# Module_main.net
KiCad netlist of a schematic drawn in Altium Designer
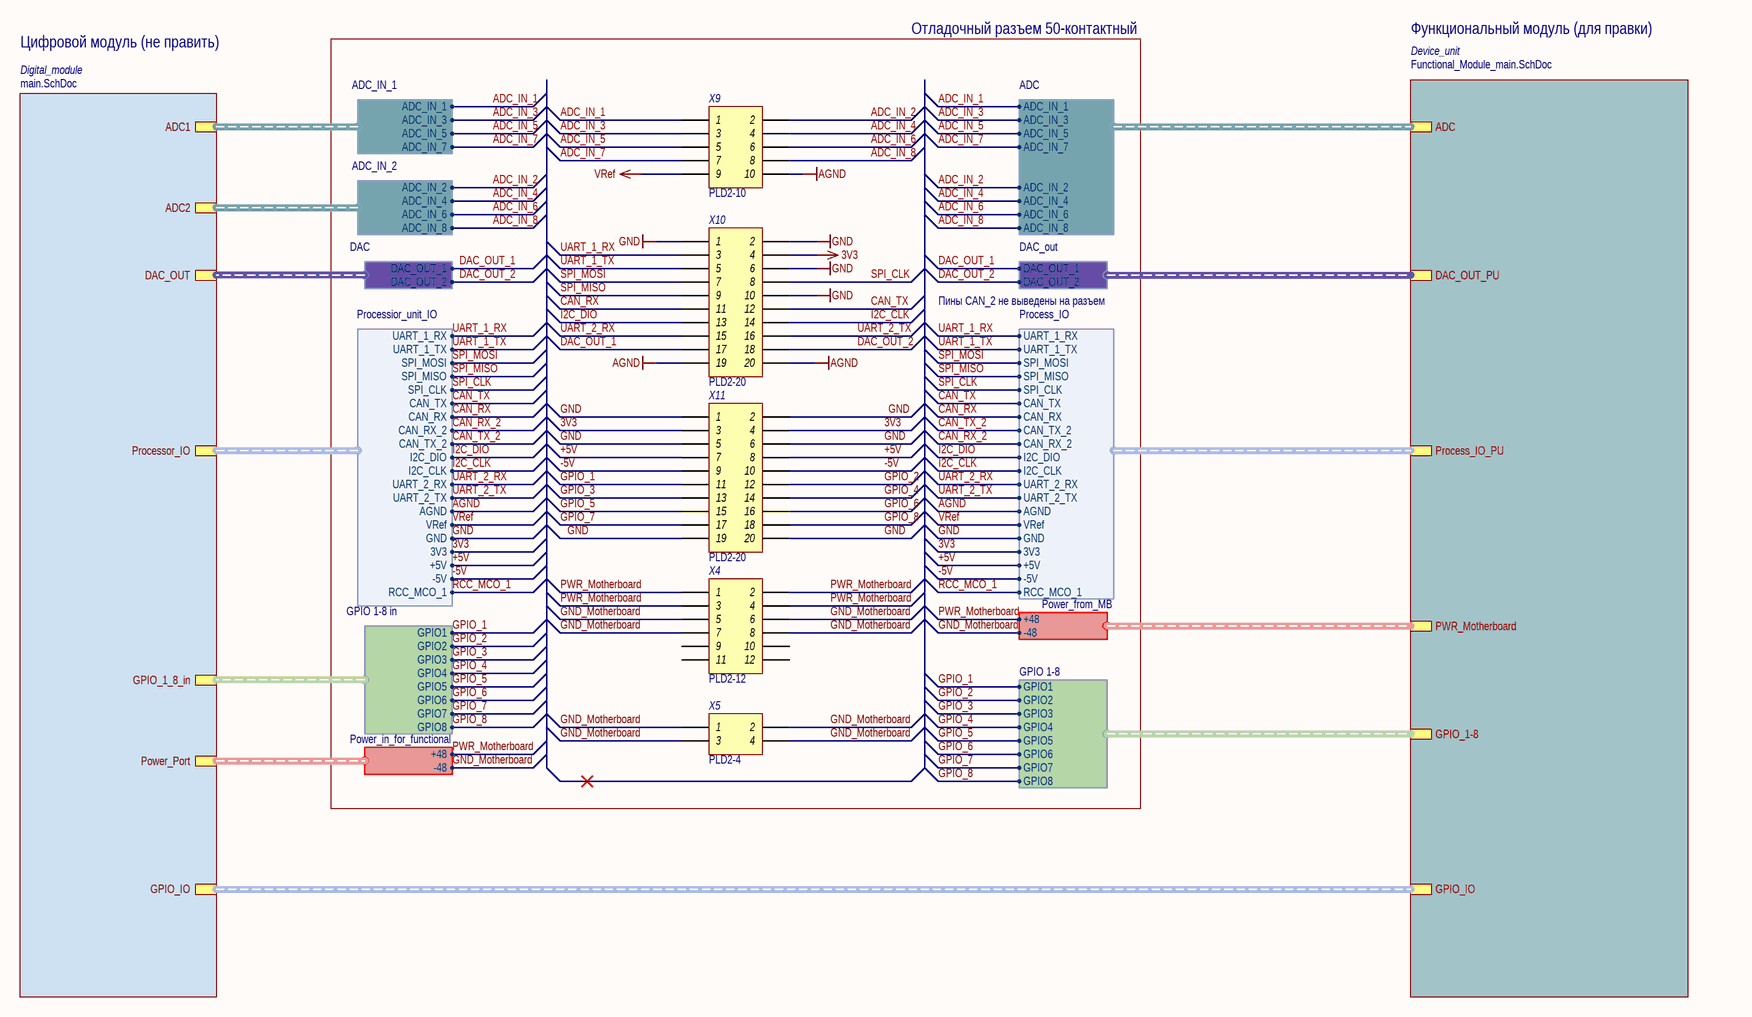
[diagram p0: Module_main.SchDoc]

(export (version "E")
  (design (tool "Eeschema 10.0.6"))
  (components
    (comp (ref "X4")
      (value "Header 2X6")
      (footprint "PLD2-12R 2.54")
      (description "Header, 12-Pin, Dual row")
      (fields (field (name "НАИМЕНОВАНИЕ") "PLD2-12"))
      (libsource (lib "Connector") (part "PLD2-12"))
    )
    (comp (ref "X5")
      (value "Header 2X4")
      (footprint "PLD2-4 R 2.54")
      (description "Header, 4-Pin, Dual row")
      (fields (field (name "НАИМЕНОВАНИЕ") "PLD2-4"))
      (libsource (lib "Connector") (part "PLD2-4"))
    )
    (comp (ref "X9")
      (value "Header 2X10")
      (footprint "PBD2-10s")
      (description "Header, 10-Pin, Dual row")
      (fields (field (name "НАИМЕНОВАНИЕ") "PLD2-10"))
      (libsource (lib "Connector") (part "PLD2-10"))
    )
    (comp (ref "X10")
      (value "Header 2X10")
      (footprint "PBD2-20s")
      (description "Header, 12-Pin, Dual row")
      (fields (field (name "НАИМЕНОВАНИЕ") "PLD2-20"))
      (libsource (lib "Connector") (part "PLD2-20"))
    )
    (comp (ref "X11")
      (value "Header 2X10")
      (footprint "PBD2-20s")
      (description "Header, 12-Pin, Dual row")
      (fields (field (name "НАИМЕНОВАНИЕ") "PLD2-20"))
      (libsource (lib "Connector") (part "PLD2-20"))
    )
  )
  (nets
    (net (code "11") (name "/+5V") (class "Default")
      (node (ref "X11") (pin "7") (pinfunction "7_7") (pintype "passive"))
      (node (ref "X11") (pin "8") (pinfunction "8_8") (pintype "passive"))
    )
    (net (code "12") (name "/-5V") (class "Default")
      (node (ref "X11") (pin "10") (pinfunction "10_10") (pintype "passive"))
      (node (ref "X11") (pin "9") (pinfunction "9_9") (pintype "passive"))
    )
    (net (code "13") (name "/ADC_IN_1") (class "Default")
      (node (ref "X9") (pin "1") (pinfunction "1_1") (pintype "passive"))
    )
    (net (code "14") (name "/ADC_IN_2") (class "Default")
      (node (ref "X9") (pin "2") (pinfunction "2_2") (pintype "passive"))
    )
    (net (code "15") (name "/ADC_IN_3") (class "Default")
      (node (ref "X9") (pin "3") (pinfunction "3_3") (pintype "passive"))
    )
    (net (code "16") (name "/ADC_IN_4") (class "Default")
      (node (ref "X9") (pin "4") (pinfunction "4_4") (pintype "passive"))
    )
    (net (code "17") (name "/ADC_IN_5") (class "Default")
      (node (ref "X9") (pin "5") (pinfunction "5_5") (pintype "passive"))
    )
    (net (code "18") (name "/ADC_IN_6") (class "Default")
      (node (ref "X9") (pin "6") (pinfunction "6_6") (pintype "passive"))
    )
    (net (code "19") (name "/ADC_IN_7") (class "Default")
      (node (ref "X9") (pin "7") (pinfunction "7_7") (pintype "passive"))
    )
    (net (code "20") (name "/ADC_IN_8") (class "Default")
      (node (ref "X9") (pin "8") (pinfunction "8_8") (pintype "passive"))
    )
    (net (code "21") (name "/CAN_RX") (class "Default")
      (node (ref "X10") (pin "11") (pinfunction "11_11") (pintype "passive"))
    )
    (net (code "23") (name "/CAN_TX") (class "Default")
      (node (ref "X10") (pin "12") (pinfunction "12_12") (pintype "passive"))
    )
    (net (code "25") (name "/DAC_OUT_1") (class "Default")
      (node (ref "X10") (pin "17") (pinfunction "17_17") (pintype "passive"))
    )
    (net (code "26") (name "/DAC_OUT_2") (class "Default")
      (node (ref "X10") (pin "18") (pinfunction "18_18") (pintype "passive"))
    )
    (net (code "27") (name "/GND_Motherboard") (class "Default")
      (node (ref "X4") (pin "5") (pinfunction "5_5") (pintype "passive"))
      (node (ref "X4") (pin "6") (pinfunction "6_6") (pintype "passive"))
      (node (ref "X4") (pin "7") (pinfunction "7_7") (pintype "passive"))
      (node (ref "X4") (pin "8") (pinfunction "8_8") (pintype "passive"))
      (node (ref "X5") (pin "1") (pinfunction "1_1") (pintype "passive"))
      (node (ref "X5") (pin "2") (pinfunction "2_2") (pintype "passive"))
      (node (ref "X5") (pin "3") (pinfunction "3_3") (pintype "passive"))
      (node (ref "X5") (pin "4") (pinfunction "4_4") (pintype "passive"))
    )
    (net (code "28") (name "/GPIO_1") (class "Default")
      (node (ref "X11") (pin "11") (pinfunction "11_11") (pintype "passive"))
    )
    (net (code "29") (name "/GPIO_2") (class "Default")
      (node (ref "X11") (pin "12") (pinfunction "12_12") (pintype "passive"))
    )
    (net (code "30") (name "/GPIO_3") (class "Default")
      (node (ref "X11") (pin "13") (pinfunction "13_13") (pintype "passive"))
    )
    (net (code "31") (name "/GPIO_4") (class "Default")
      (node (ref "X11") (pin "14") (pinfunction "14_14") (pintype "passive"))
    )
    (net (code "32") (name "/GPIO_5") (class "Default")
      (node (ref "X11") (pin "15") (pinfunction "15_15") (pintype "passive"))
    )
    (net (code "33") (name "/GPIO_6") (class "Default")
      (node (ref "X11") (pin "16") (pinfunction "16_16") (pintype "passive"))
    )
    (net (code "34") (name "/GPIO_7") (class "Default")
      (node (ref "X11") (pin "17") (pinfunction "17_17") (pintype "passive"))
    )
    (net (code "35") (name "/GPIO_8") (class "Default")
      (node (ref "X11") (pin "18") (pinfunction "18_18") (pintype "passive"))
    )
    (net (code "37") (name "/I2C_CLK") (class "Default")
      (node (ref "X10") (pin "14") (pinfunction "14_14") (pintype "passive"))
    )
    (net (code "38") (name "/I2C_DIO") (class "Default")
      (node (ref "X10") (pin "13") (pinfunction "13_13") (pintype "passive"))
    )
    (net (code "39") (name "/PWR_Motherboard") (class "Default")
      (node (ref "X4") (pin "1") (pinfunction "1_1") (pintype "passive"))
      (node (ref "X4") (pin "2") (pinfunction "2_2") (pintype "passive"))
      (node (ref "X4") (pin "3") (pinfunction "3_3") (pintype "passive"))
      (node (ref "X4") (pin "4") (pinfunction "4_4") (pintype "passive"))
    )
    (net (code "41") (name "/SPI_CLK") (class "Default")
      (node (ref "X10") (pin "8") (pinfunction "8_8") (pintype "passive"))
    )
    (net (code "42") (name "/SPI_MISO") (class "Default")
      (node (ref "X10") (pin "9") (pinfunction "9_9") (pintype "passive"))
    )
    (net (code "43") (name "/SPI_MOSI") (class "Default")
      (node (ref "X10") (pin "7") (pinfunction "7_7") (pintype "passive"))
    )
    (net (code "44") (name "/UART_1_RX") (class "Default")
      (node (ref "X10") (pin "3") (pinfunction "3_3") (pintype "passive"))
    )
    (net (code "45") (name "/UART_1_TX") (class "Default")
      (node (ref "X10") (pin "5") (pinfunction "5_5") (pintype "passive"))
    )
    (net (code "46") (name "/UART_2_RX") (class "Default")
      (node (ref "X10") (pin "15") (pinfunction "15_15") (pintype "passive"))
    )
    (net (code "47") (name "/UART_2_TX") (class "Default")
      (node (ref "X10") (pin "16") (pinfunction "16_16") (pintype "passive"))
    )
    (net (code "59") (name "3V3") (class "Default")
      (node (ref "X10") (pin "4") (pinfunction "4_4") (pintype "passive"))
      (node (ref "X11") (pin "3") (pinfunction "3_3") (pintype "passive"))
      (node (ref "X11") (pin "4") (pinfunction "4_4") (pintype "passive"))
    )
    (net (code "60") (name "AGND") (class "Default")
      (node (ref "X10") (pin "19") (pinfunction "19_19") (pintype "passive"))
      (node (ref "X10") (pin "20") (pinfunction "20_20") (pintype "passive"))
      (node (ref "X9") (pin "10") (pinfunction "10_10") (pintype "passive"))
    )
    (net (code "61") (name "GND") (class "Default")
      (node (ref "X10") (pin "1") (pinfunction "1_1") (pintype "passive"))
      (node (ref "X10") (pin "10") (pinfunction "10_10") (pintype "passive"))
      (node (ref "X10") (pin "2") (pinfunction "2_2") (pintype "passive"))
      (node (ref "X10") (pin "6") (pinfunction "6_6") (pintype "passive"))
      (node (ref "X11") (pin "1") (pinfunction "1_1") (pintype "passive"))
      (node (ref "X11") (pin "19") (pinfunction "19_19") (pintype "passive"))
      (node (ref "X11") (pin "2") (pinfunction "2_2") (pintype "passive"))
      (node (ref "X11") (pin "20") (pinfunction "20_20") (pintype "passive"))
      (node (ref "X11") (pin "5") (pinfunction "5_5") (pintype "passive"))
      (node (ref "X11") (pin "6") (pinfunction "6_6") (pintype "passive"))
    )
    (net (code "62") (name "VRef") (class "Default")
      (node (ref "X9") (pin "9") (pinfunction "9_9") (pintype "passive"))
    )
    (net (code "63") (name "unconnected-(X4-Pad9)") (class "Default")
      (node (ref "X4") (pin "9") (pinfunction "9_9") (pintype "passive"))
    )
    (net (code "64") (name "unconnected-(X4-Pad10)") (class "Default")
      (node (ref "X4") (pin "10") (pinfunction "10_10") (pintype "passive"))
    )
    (net (code "65") (name "unconnected-(X4-Pad11)") (class "Default")
      (node (ref "X4") (pin "11") (pinfunction "11_11") (pintype "passive"))
    )
    (net (code "66") (name "unconnected-(X4-Pad12)") (class "Default")
      (node (ref "X4") (pin "12") (pinfunction "12_12") (pintype "passive"))
    )
  )
)
